# JW3651_PCB.net
KiCad netlist of a schematic drawn in Altium Designer
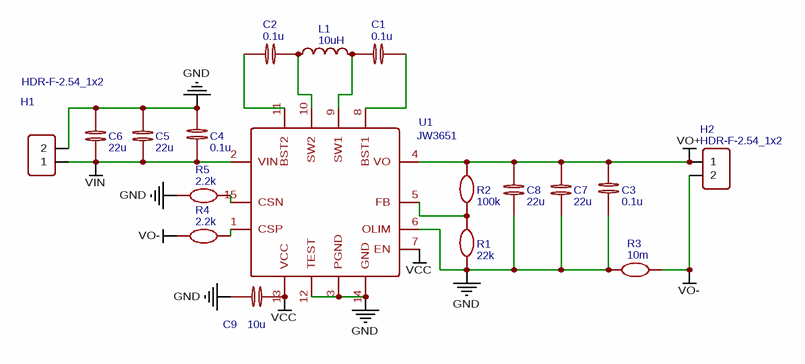
[diagram p0: JW3651原理图与PCB.schdoc]

(export (version "E")
  (design (tool "Eeschema 10.0.6"))
  (components
    (comp (ref "C1")
      (value "0.1u")
      (footprint "C0603")
      (fields (field (name "CONTRIBUTOR") "LCEDA_Lib"))
      (libsource (lib "altium-import") (part "root_0_0.1u_"))
    )
    (comp (ref "C2")
      (value "0.1u")
      (footprint "C0603")
      (fields (field (name "CONTRIBUTOR") "LCEDA_Lib"))
      (libsource (lib "altium-import") (part "root_0_0.1u_"))
    )
    (comp (ref "C3")
      (value "0.1u")
      (footprint "C0603")
      (fields (field (name "CONTRIBUTOR") "LCEDA_Lib"))
      (libsource (lib "altium-import") (part "root_3_0.1u_"))
    )
    (comp (ref "C4")
      (value "0.1u")
      (footprint "C0603")
      (fields (field (name "CONTRIBUTOR") "LCEDA_Lib"))
      (libsource (lib "altium-import") (part "root_3_0.1u_"))
    )
    (comp (ref "C5")
      (value "22u")
      (footprint "C0805")
      (fields (field (name "CONTRIBUTOR") "LCEDA_Lib"))
      (libsource (lib "altium-import") (part "root_1_22u_"))
    )
    (comp (ref "C6")
      (value "22u")
      (footprint "C0805")
      (fields (field (name "CONTRIBUTOR") "LCEDA_Lib"))
      (libsource (lib "altium-import") (part "root_1_22u_"))
    )
    (comp (ref "C7")
      (value "22u")
      (footprint "C0805")
      (fields (field (name "CONTRIBUTOR") "LCEDA_Lib"))
      (libsource (lib "altium-import") (part "root_1_22u_"))
    )
    (comp (ref "C8")
      (value "22u")
      (footprint "C0805")
      (fields (field (name "CONTRIBUTOR") "LCEDA_Lib"))
      (libsource (lib "altium-import") (part "root_1_22u_"))
    )
    (comp (ref "C9")
      (value "10u")
      (footprint "C0603")
      (fields (field (name "CONTRIBUTOR") "LCEDA_Lib"))
      (libsource (lib "altium-import") (part "root_0_10u_"))
    )
    (comp (ref "H1")
      (value "HDR-F-2.54_1x2")
      (footprint "HDR-F-2.54_1X2")
      (fields (field (name "CONTRIBUTOR") "LCEDA_Lib"))
      (libsource (lib "altium-import") (part "root_2_HDR-F-2.54_1x2_"))
    )
    (comp (ref "H2")
      (value "HDR-F-2.54_1x2")
      (footprint "HDR-F-2.54_1X2")
      (fields (field (name "CONTRIBUTOR") "LCEDA_Lib"))
      (libsource (lib "altium-import") (part "root_0_HDR-F-2.54_1x2_"))
    )
    (comp (ref "L1")
      (value "10uH")
      (footprint "IND-SMD_L5.4-W5.2_FXL0530")
      (fields (field (name "MANUFACTURER PART") "FXL0530-100-M") (field (name "CONTRIBUTOR") "wuzhixiong"))
      (libsource (lib "altium-import") (part "root_0_10uH_"))
    )
    (comp (ref "R1")
      (value "22k")
      (footprint "R0603")
      (fields (field (name "CONTRIBUTOR") "LCEDA_Lib"))
      (libsource (lib "altium-import") (part "root_1_22k_"))
    )
    (comp (ref "R2")
      (value "100k")
      (footprint "R0603")
      (fields (field (name "CONTRIBUTOR") "LCEDA_Lib"))
      (libsource (lib "altium-import") (part "root_1_100k_"))
    )
    (comp (ref "R3")
      (value "10m")
      (footprint "R1206")
      (fields (field (name "CONTRIBUTOR") "LCEDA_Lib"))
      (libsource (lib "altium-import") (part "root_0_10m_"))
    )
    (comp (ref "R4")
      (value "2.2k")
      (footprint "R0603")
      (fields (field (name "CONTRIBUTOR") "LCEDA_Lib"))
      (libsource (lib "altium-import") (part "root_2_2.2k_"))
    )
    (comp (ref "R5")
      (value "2.2k")
      (footprint "R0603")
      (fields (field (name "CONTRIBUTOR") "LCEDA_Lib"))
      (libsource (lib "altium-import") (part "root_2_2.2k_"))
    )
    (comp (ref "U1")
      (value "JW3651")
      (footprint "JW3651")
      (libsource (lib "altium-import") (part "root_0_JW3651_"))
    )
  )
  (nets
    (net (code "1") (name "GND") (class "Default")
      (node (ref "C3") (pin "2") (pinfunction "2_2") (pintype "passive"))
      (node (ref "C4") (pin "1") (pinfunction "1_1") (pintype "passive"))
      (node (ref "C5") (pin "2") (pinfunction "2_2") (pintype "passive"))
      (node (ref "C6") (pin "2") (pinfunction "2_2") (pintype "passive"))
      (node (ref "C7") (pin "1") (pinfunction "1_1") (pintype "passive"))
      (node (ref "C8") (pin "1") (pinfunction "1_1") (pintype "passive"))
      (node (ref "C9") (pin "1") (pinfunction "1_1") (pintype "passive"))
      (node (ref "H1") (pin "2") (pinfunction "2_2") (pintype "passive"))
      (node (ref "R1") (pin "1") (pinfunction "1_1") (pintype "passive"))
      (node (ref "R3") (pin "1") (pinfunction "1_1") (pintype "passive"))
      (node (ref "R5") (pin "2") (pinfunction "2_2") (pintype "passive"))
      (node (ref "U1") (pin "12") (pinfunction "TEST_12") (pintype "passive"))
      (node (ref "U1") (pin "14") (pinfunction "GND_14") (pintype "passive"))
      (node (ref "U1") (pin "3") (pinfunction "PGND_3") (pintype "passive"))
      (node (ref "U1") (pin "6") (pinfunction "OLIM_6") (pintype "passive"))
    )
    (net (code "2") (name "Net-(U1-BST1)") (class "Default")
      (node (ref "C1") (pin "2") (pinfunction "2_2") (pintype "passive"))
      (node (ref "U1") (pin "8") (pinfunction "BST1_8") (pintype "passive"))
    )
    (net (code "3") (name "Net-(U1-BST2)") (class "Default")
      (node (ref "C2") (pin "1") (pinfunction "1_1") (pintype "passive"))
      (node (ref "U1") (pin "11") (pinfunction "BST2_11") (pintype "passive"))
    )
    (net (code "4") (name "Net-(U1-CSN)") (class "Default")
      (node (ref "R5") (pin "1") (pinfunction "1_1") (pintype "passive"))
      (node (ref "U1") (pin "15") (pinfunction "CSN_15") (pintype "passive"))
    )
    (net (code "5") (name "Net-(U1-CSP)") (class "Default")
      (node (ref "R4") (pin "1") (pinfunction "1_1") (pintype "passive"))
      (node (ref "U1") (pin "1") (pinfunction "CSP_1") (pintype "passive"))
    )
    (net (code "6") (name "Net-(U1-FB)") (class "Default")
      (node (ref "R1") (pin "2") (pinfunction "2_2") (pintype "passive"))
      (node (ref "R2") (pin "1") (pinfunction "1_1") (pintype "passive"))
      (node (ref "U1") (pin "5") (pinfunction "FB_5") (pintype "passive"))
    )
    (net (code "7") (name "Net-(U1-SW1)") (class "Default")
      (node (ref "C1") (pin "1") (pinfunction "1_1") (pintype "passive"))
      (node (ref "L1") (pin "2") (pinfunction "2_2") (pintype "passive"))
      (node (ref "U1") (pin "9") (pinfunction "SW1_9") (pintype "passive"))
    )
    (net (code "8") (name "Net-(U1-SW2)") (class "Default")
      (node (ref "C2") (pin "2") (pinfunction "2_2") (pintype "passive"))
      (node (ref "L1") (pin "1") (pinfunction "1_1") (pintype "passive"))
      (node (ref "U1") (pin "10") (pinfunction "SW2_10") (pintype "passive"))
    )
    (net (code "9") (name "VCC") (class "Default")
      (node (ref "C9") (pin "2") (pinfunction "2_2") (pintype "passive"))
      (node (ref "U1") (pin "13") (pinfunction "VCC_13") (pintype "passive"))
      (node (ref "U1") (pin "7") (pinfunction "EN_7") (pintype "passive"))
    )
    (net (code "10") (name "VIN") (class "Default")
      (node (ref "C4") (pin "2") (pinfunction "2_2") (pintype "passive"))
      (node (ref "C5") (pin "1") (pinfunction "1_1") (pintype "passive"))
      (node (ref "C6") (pin "1") (pinfunction "1_1") (pintype "passive"))
      (node (ref "H1") (pin "1") (pinfunction "1_1") (pintype "passive"))
      (node (ref "U1") (pin "2") (pinfunction "VIN_2") (pintype "passive"))
    )
    (net (code "11") (name "VO+") (class "Default")
      (node (ref "C3") (pin "1") (pinfunction "1_1") (pintype "passive"))
      (node (ref "C7") (pin "2") (pinfunction "2_2") (pintype "passive"))
      (node (ref "C8") (pin "2") (pinfunction "2_2") (pintype "passive"))
      (node (ref "H2") (pin "1") (pinfunction "1_1") (pintype "passive"))
      (node (ref "R2") (pin "2") (pinfunction "2_2") (pintype "passive"))
      (node (ref "U1") (pin "4") (pinfunction "VO_4") (pintype "passive"))
    )
    (net (code "12") (name "VO-") (class "Default")
      (node (ref "H2") (pin "2") (pinfunction "2_2") (pintype "passive"))
      (node (ref "R3") (pin "2") (pinfunction "2_2") (pintype "passive"))
      (node (ref "R4") (pin "2") (pinfunction "2_2") (pintype "passive"))
    )
  )
)
